# Nmos.net
KiCad netlist of a schematic drawn in Altium Designer
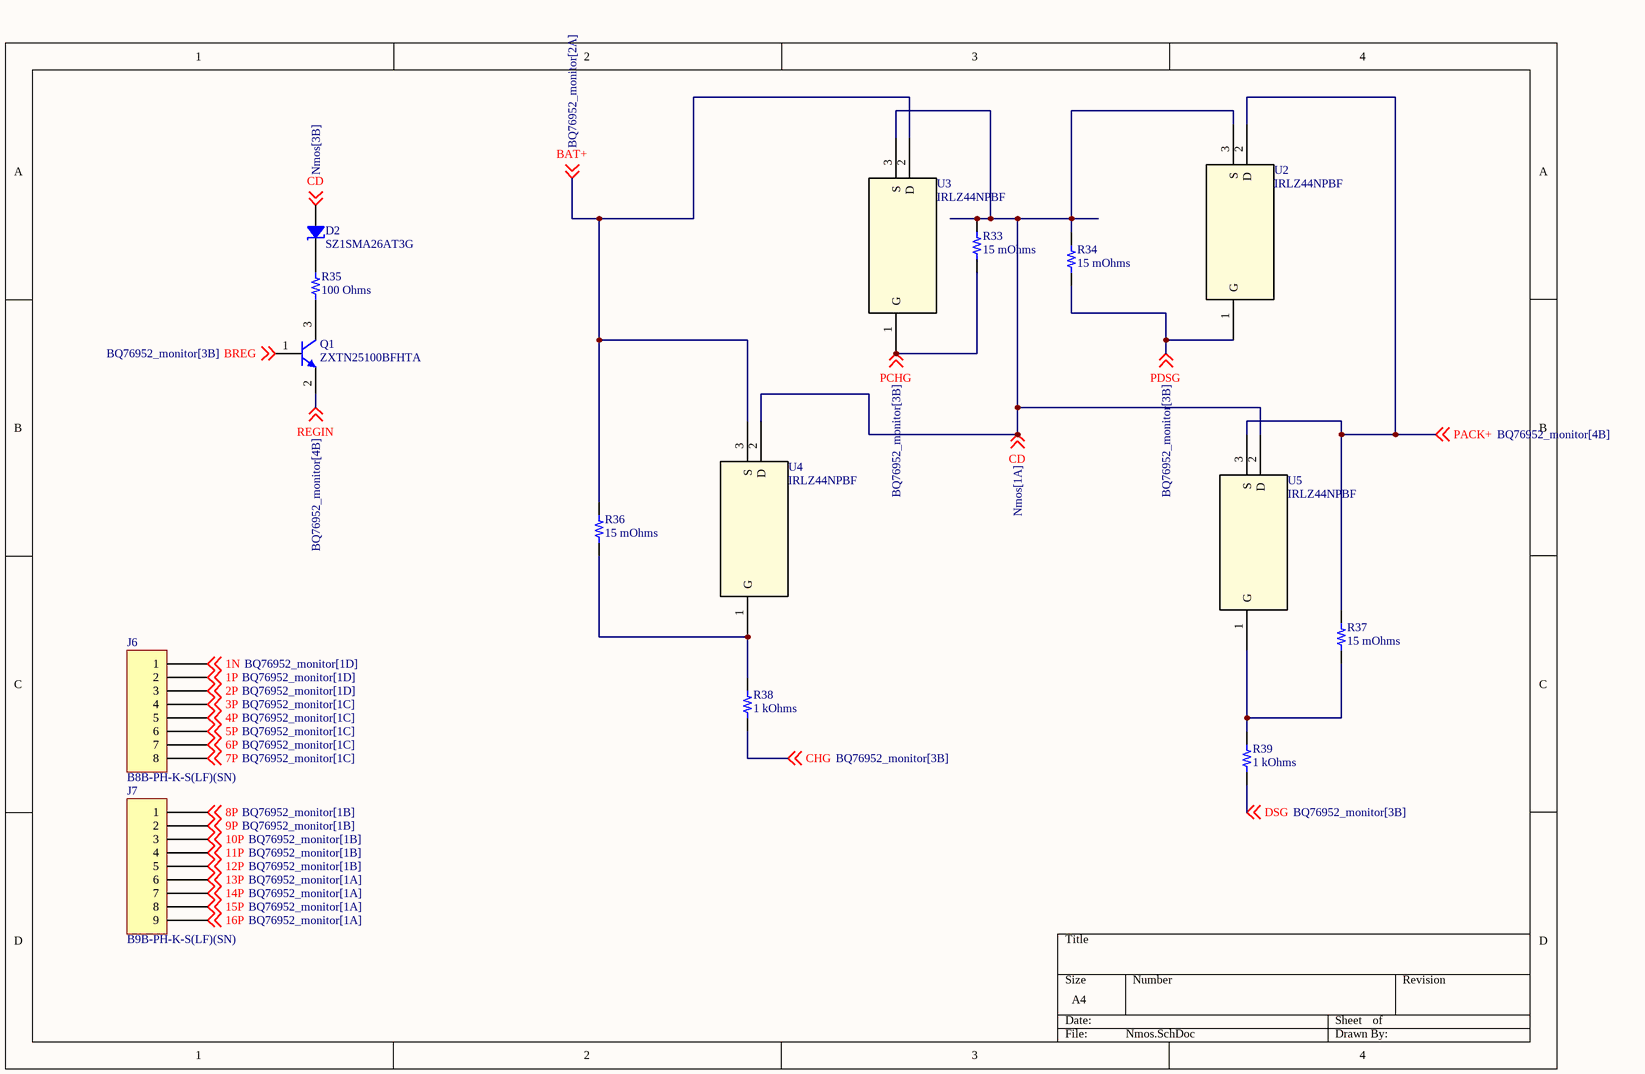
[diagram p0: Nmos.SchDoc]

(export (version "E")
  (design (tool "Eeschema 10.0.6"))
  (components
    (comp (ref "D2")
      (value "SZ1SMA26AT3G")
      (footprint "DO214AC SMA")
      (description "TVS DIODE 26VWM 42.1VC SMA")
      (fields (field (name "MANUFACTURER") "Littelfuse Inc."))
      (libsource (lib "Celestial Altium Library - altium_library (1)") (part "DIODE TVS UNI"))
    )
    (comp (ref "J6")
      (value "B8B-PH-K-S(LF)(SN)")
      (footprint "JST B8B-PH-K")
      (description "CONN HEADER VERT 8POS 2MM")
      (fields (field (name "MANUFACTURER") "JST Sales America Inc."))
      (libsource (lib "Celestial Altium Library - altium_library (1)") (part "8 Pin"))
    )
    (comp (ref "J7")
      (value "B9B-PH-K-S(LF)(SN)")
      (footprint "JST B9B-PH-K")
      (description "CONN HEADER VERT 9POS 2MM")
      (fields (field (name "MANUFACTURER") "JST Sales America Inc."))
      (libsource (lib "Celestial Altium Library - altium_library (1)") (part "9 Pin"))
    )
    (comp (ref "Q1")
      (value "ZXTN25100BFHTA")
      (footprint "DIODES SOT-23-3")
      (description "TRANS NPN 100V 3A SOT23-3")
      (fields (field (name "MANUFACTURER") "Diodes Incorporated"))
      (libsource (lib "Celestial Altium Library - altium_library (1)") (part "DIODES INC NPN SOT-23-3"))
    )
    (comp (ref "R33")
      (value "15 mOhms")
      (footprint "RES 1206_3216")
      (description "RES 15M OHM 1% 1.5W 1206")
      (fields
        (field (name "PART NUMBER") "TLR2BPDTD15L0F75")
        (field (name "MANUFACTURER") "KOA Speer Electronics, Inc.")
      )
      (libsource (lib "Celestial Altium Library - altium_library (1)") (part "Resistor"))
    )
    (comp (ref "R34")
      (value "15 mOhms")
      (footprint "RES 1206_3216")
      (description "RES 15M OHM 1% 1.5W 1206")
      (fields
        (field (name "PART NUMBER") "TLR2BPDTD15L0F75")
        (field (name "MANUFACTURER") "KOA Speer Electronics, Inc.")
      )
      (libsource (lib "Celestial Altium Library - altium_library (1)") (part "Resistor"))
    )
    (comp (ref "R35")
      (value "100 Ohms")
      (footprint "RES 1206_3216")
      (description "RES 100 OHM 0.1% 1/8W 1206")
      (fields
        (field (name "PART NUMBER") "RNCS1206BKE100R")
        (field (name "MANUFACTURER") "Stackpole Electronics Inc")
      )
      (libsource (lib "Celestial Altium Library - altium_library (1)") (part "Resistor"))
    )
    (comp (ref "R36")
      (value "15 mOhms")
      (footprint "RES 1206_3216")
      (description "RES 15M OHM 1% 1.5W 1206")
      (fields
        (field (name "PART NUMBER") "TLR2BPDTD15L0F75")
        (field (name "MANUFACTURER") "KOA Speer Electronics, Inc.")
      )
      (libsource (lib "Celestial Altium Library - altium_library (1)") (part "Resistor"))
    )
    (comp (ref "R37")
      (value "15 mOhms")
      (footprint "RES 1206_3216")
      (description "RES 15M OHM 1% 1.5W 1206")
      (fields
        (field (name "PART NUMBER") "TLR2BPDTD15L0F75")
        (field (name "MANUFACTURER") "KOA Speer Electronics, Inc.")
      )
      (libsource (lib "Celestial Altium Library - altium_library (1)") (part "Resistor"))
    )
    (comp (ref "R38")
      (value "1 kOhms")
      (footprint "RES 1206_3216")
      (description "RES 1K OHM 1% 1/4W 1206")
      (fields
        (field (name "PART NUMBER") "CRGCQ1206F1K0")
        (field (name "MANUFACTURER") "TE Connectivity Passive Product")
      )
      (libsource (lib "Celestial Altium Library - altium_library (1)") (part "Resistor"))
    )
    (comp (ref "R39")
      (value "1 kOhms")
      (footprint "RES 1206_3216")
      (description "RES 1K OHM 1% 1/4W 1206")
      (fields
        (field (name "PART NUMBER") "CRGCQ1206F1K0")
        (field (name "MANUFACTURER") "TE Connectivity Passive Product")
      )
      (libsource (lib "Celestial Altium Library - altium_library (1)") (part "Resistor"))
    )
    (comp (ref "U2")
      (value "IRLZ44NPBF")
      (footprint "PG-TO220-3_INF")
      (description "No Description Available")
      (libsource (lib "IRLZ44NPBF") (part "IRLZ44NPBF"))
    )
    (comp (ref "U3")
      (value "IRLZ44NPBF")
      (footprint "PG-TO220-3_INF")
      (description "No Description Available")
      (libsource (lib "IRLZ44NPBF") (part "IRLZ44NPBF"))
    )
    (comp (ref "U4")
      (value "IRLZ44NPBF")
      (footprint "PG-TO220-3_INF")
      (description "No Description Available")
      (libsource (lib "IRLZ44NPBF") (part "IRLZ44NPBF"))
    )
    (comp (ref "U5")
      (value "IRLZ44NPBF")
      (footprint "PG-TO220-3_INF")
      (description "No Description Available")
      (libsource (lib "IRLZ44NPBF") (part "IRLZ44NPBF"))
    )
  )
  (nets
    (net (code "1") (name "1N") (class "Default")
      (node (ref "J6") (pin "1") (pinfunction "1_1") (pintype "passive"))
    )
    (net (code "2") (name "1P") (class "Default")
      (node (ref "J6") (pin "2") (pinfunction "2_2") (pintype "passive"))
    )
    (net (code "3") (name "2P") (class "Default")
      (node (ref "J6") (pin "3") (pinfunction "3_3") (pintype "passive"))
    )
    (net (code "4") (name "3P") (class "Default")
      (node (ref "J6") (pin "4") (pinfunction "4_4") (pintype "passive"))
    )
    (net (code "5") (name "4P") (class "Default")
      (node (ref "J6") (pin "5") (pinfunction "5_5") (pintype "passive"))
    )
    (net (code "6") (name "5P") (class "Default")
      (node (ref "J6") (pin "6") (pinfunction "6_6") (pintype "passive"))
    )
    (net (code "7") (name "6P") (class "Default")
      (node (ref "J6") (pin "7") (pinfunction "7_7") (pintype "passive"))
    )
    (net (code "8") (name "7P") (class "Default")
      (node (ref "J6") (pin "8") (pinfunction "8_8") (pintype "passive"))
    )
    (net (code "9") (name "8P") (class "Default")
      (node (ref "J7") (pin "1") (pinfunction "1_1") (pintype "passive"))
    )
    (net (code "10") (name "9P") (class "Default")
      (node (ref "J7") (pin "2") (pinfunction "2_2") (pintype "passive"))
    )
    (net (code "11") (name "10P") (class "Default")
      (node (ref "J7") (pin "3") (pinfunction "3_3") (pintype "passive"))
    )
    (net (code "12") (name "11P") (class "Default")
      (node (ref "J7") (pin "4") (pinfunction "4_4") (pintype "passive"))
    )
    (net (code "13") (name "12P") (class "Default")
      (node (ref "J7") (pin "5") (pinfunction "5_5") (pintype "passive"))
    )
    (net (code "14") (name "13P") (class "Default")
      (node (ref "J7") (pin "6") (pinfunction "6_6") (pintype "passive"))
    )
    (net (code "15") (name "14P") (class "Default")
      (node (ref "J7") (pin "7") (pinfunction "7_7") (pintype "passive"))
    )
    (net (code "16") (name "15P") (class "Default")
      (node (ref "J7") (pin "8") (pinfunction "8_8") (pintype "passive"))
    )
    (net (code "17") (name "16P") (class "Default")
      (node (ref "J7") (pin "9") (pinfunction "9_9") (pintype "passive"))
    )
    (net (code "18") (name "BAT+") (class "Default")
      (node (ref "R36") (pin "2") (pinfunction "2_2") (pintype "passive"))
      (node (ref "U3") (pin "2") (pinfunction "D_2") (pintype "passive"))
      (node (ref "U4") (pin "3") (pinfunction "S_3") (pintype "passive"))
    )
    (net (code "19") (name "BREG") (class "Default")
      (node (ref "Q1") (pin "1") (pinfunction "B_1") (pintype "passive"))
    )
    (net (code "20") (name "CD") (class "Default")
      (node (ref "D2") (pin "1") (pinfunction "1_1") (pintype "passive"))
      (node (ref "R33") (pin "2") (pinfunction "2_2") (pintype "passive"))
      (node (ref "R34") (pin "2") (pinfunction "2_2") (pintype "passive"))
      (node (ref "U2") (pin "3") (pinfunction "S_3") (pintype "passive"))
      (node (ref "U3") (pin "3") (pinfunction "S_3") (pintype "passive"))
      (node (ref "U4") (pin "2") (pinfunction "D_2") (pintype "passive"))
      (node (ref "U5") (pin "2") (pinfunction "D_2") (pintype "passive"))
    )
    (net (code "21") (name "CHG") (class "Default")
      (node (ref "R38") (pin "1") (pinfunction "1_1") (pintype "passive"))
    )
    (net (code "22") (name "DSG") (class "Default")
      (node (ref "R39") (pin "1") (pinfunction "1_1") (pintype "passive"))
    )
    (net (code "23") (name "Net-(D2-Pad2)") (class "Default")
      (node (ref "D2") (pin "2") (pinfunction "2_2") (pintype "passive"))
      (node (ref "R35") (pin "2") (pinfunction "2_2") (pintype "passive"))
    )
    (net (code "24") (name "Net-(Q1-C)") (class "Default")
      (node (ref "Q1") (pin "3") (pinfunction "C_3") (pintype "passive"))
      (node (ref "R35") (pin "1") (pinfunction "1_1") (pintype "passive"))
    )
    (net (code "25") (name "Net-(U4-G)") (class "Default")
      (node (ref "R36") (pin "1") (pinfunction "1_1") (pintype "passive"))
      (node (ref "R38") (pin "2") (pinfunction "2_2") (pintype "passive"))
      (node (ref "U4") (pin "1") (pinfunction "G_1") (pintype "passive"))
    )
    (net (code "26") (name "Net-(U5-G)") (class "Default")
      (node (ref "R37") (pin "1") (pinfunction "1_1") (pintype "passive"))
      (node (ref "R39") (pin "2") (pinfunction "2_2") (pintype "passive"))
      (node (ref "U5") (pin "1") (pinfunction "G_1") (pintype "passive"))
    )
    (net (code "27") (name "PACK+") (class "Default")
      (node (ref "R37") (pin "2") (pinfunction "2_2") (pintype "passive"))
      (node (ref "U2") (pin "2") (pinfunction "D_2") (pintype "passive"))
      (node (ref "U5") (pin "3") (pinfunction "S_3") (pintype "passive"))
    )
    (net (code "28") (name "PCHG") (class "Default")
      (node (ref "R33") (pin "1") (pinfunction "1_1") (pintype "passive"))
      (node (ref "U3") (pin "1") (pinfunction "G_1") (pintype "passive"))
    )
    (net (code "29") (name "PDSG") (class "Default")
      (node (ref "R34") (pin "1") (pinfunction "1_1") (pintype "passive"))
      (node (ref "U2") (pin "1") (pinfunction "G_1") (pintype "passive"))
    )
    (net (code "30") (name "REGIN") (class "Default")
      (node (ref "Q1") (pin "2") (pinfunction "E_2") (pintype "passive"))
    )
  )
)
